# awareness16.net
KiCad netlist of a schematic drawn in EAGLE
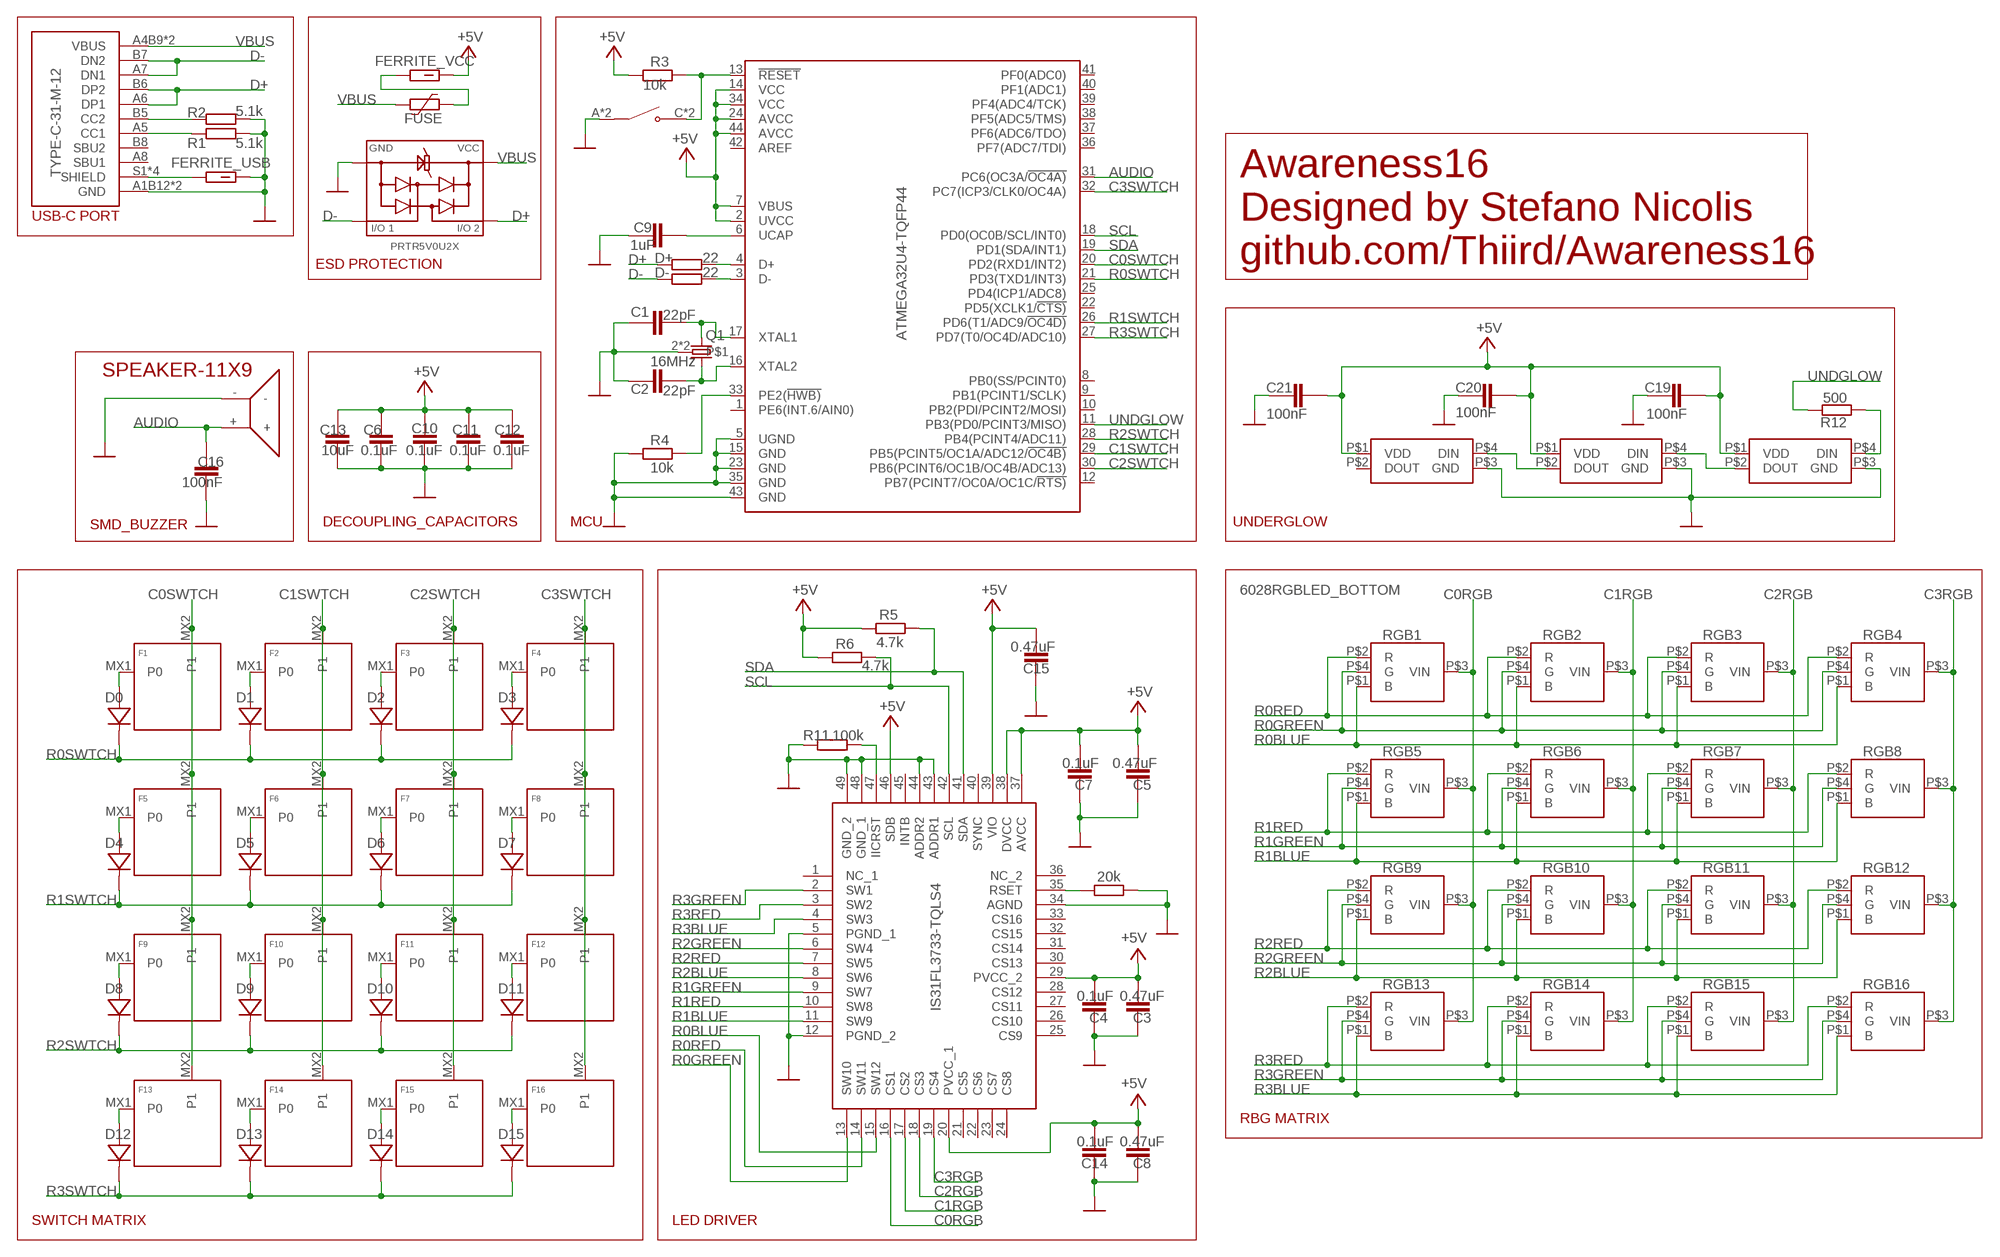
[diagram p0: schematic, sheet 1]

(export (version "E")
  (design (tool "Eeschema 10.0.6"))
  (components
    (comp (ref "C1")
      (value "22pF")
      (footprint "eagle-import:C0603")
      (libsource (lib "eagle-import") (part "CAPACITOR-0603"))
    )
    (comp (ref "C2")
      (value "22pF")
      (footprint "eagle-import:C0603")
      (libsource (lib "eagle-import") (part "CAPACITOR-0603"))
    )
    (comp (ref "C3")
      (value "0.47uF")
      (footprint "eagle-import:C0603")
      (libsource (lib "eagle-import") (part "CAPACITOR-0603"))
    )
    (comp (ref "C4")
      (value "0.1uF")
      (footprint "eagle-import:C0603")
      (libsource (lib "eagle-import") (part "CAPACITOR-0603"))
    )
    (comp (ref "C5")
      (value "0.47uF")
      (footprint "eagle-import:C0603")
      (libsource (lib "eagle-import") (part "CAPACITOR-0603"))
    )
    (comp (ref "C6")
      (value "0.1uF")
      (footprint "eagle-import:C0603")
      (libsource (lib "eagle-import") (part "CAPACITOR-0603"))
    )
    (comp (ref "C7")
      (value "0.1uF")
      (footprint "eagle-import:C0603")
      (libsource (lib "eagle-import") (part "CAPACITOR-0603"))
    )
    (comp (ref "C8")
      (value "0.47uF")
      (footprint "eagle-import:C0603")
      (libsource (lib "eagle-import") (part "CAPACITOR-0603"))
    )
    (comp (ref "C9")
      (value "1uF")
      (footprint "eagle-import:C0603")
      (libsource (lib "eagle-import") (part "CAPACITOR-0603"))
    )
    (comp (ref "C10")
      (value "0.1uF")
      (footprint "eagle-import:C0603")
      (libsource (lib "eagle-import") (part "CAPACITOR-0603"))
    )
    (comp (ref "C11")
      (value "0.1uF")
      (footprint "eagle-import:C0603")
      (libsource (lib "eagle-import") (part "CAPACITOR-0603"))
    )
    (comp (ref "C12")
      (value "0.1uF")
      (footprint "eagle-import:C0603")
      (libsource (lib "eagle-import") (part "CAPACITOR-0603"))
    )
    (comp (ref "C13")
      (value "10uF")
      (footprint "eagle-import:C0603")
      (libsource (lib "eagle-import") (part "CAPACITOR-0603"))
    )
    (comp (ref "C14")
      (value "0.1uF")
      (footprint "eagle-import:C0603")
      (libsource (lib "eagle-import") (part "CAPACITOR-0603"))
    )
    (comp (ref "C15")
      (value "0.47uF")
      (footprint "eagle-import:C0603")
      (libsource (lib "eagle-import") (part "CAPACITOR-0603"))
    )
    (comp (ref "C16")
      (value "100nF")
      (footprint "eagle-import:C0603")
      (libsource (lib "eagle-import") (part "CAPACITOR-0603"))
    )
    (comp (ref "C19")
      (value "100nF")
      (footprint "eagle-import:C0603")
      (libsource (lib "eagle-import") (part "CAPACITOR-0603"))
    )
    (comp (ref "C20")
      (value "100nF")
      (footprint "eagle-import:C0603")
      (libsource (lib "eagle-import") (part "CAPACITOR-0603"))
    )
    (comp (ref "C21")
      (value "100nF")
      (footprint "eagle-import:C0603")
      (libsource (lib "eagle-import") (part "CAPACITOR-0603"))
    )
    (comp (ref "D+")
      (value "22")
      (footprint "eagle-import:R0603")
      (libsource (lib "eagle-import") (part "RESISTOR-0603"))
    )
    (comp (ref "D-")
      (value "22")
      (footprint "eagle-import:R0603")
      (libsource (lib "eagle-import") (part "RESISTOR-0603"))
    )
    (comp (ref "D0")
      (value "DIODE-SOD-123")
      (footprint "eagle-import:SOD-123")
      (libsource (lib "eagle-import") (part "DIODE-SOD-123"))
    )
    (comp (ref "D1")
      (value "DIODE-SOD-123")
      (footprint "eagle-import:SOD-123")
      (libsource (lib "eagle-import") (part "DIODE-SOD-123"))
    )
    (comp (ref "D2")
      (value "DIODE-SOD-123")
      (footprint "eagle-import:SOD-123")
      (libsource (lib "eagle-import") (part "DIODE-SOD-123"))
    )
    (comp (ref "D3")
      (value "DIODE-SOD-123")
      (footprint "eagle-import:SOD-123")
      (libsource (lib "eagle-import") (part "DIODE-SOD-123"))
    )
    (comp (ref "D4")
      (value "DIODE-SOD-123")
      (footprint "eagle-import:SOD-123")
      (libsource (lib "eagle-import") (part "DIODE-SOD-123"))
    )
    (comp (ref "D5")
      (value "DIODE-SOD-123")
      (footprint "eagle-import:SOD-123")
      (libsource (lib "eagle-import") (part "DIODE-SOD-123"))
    )
    (comp (ref "D6")
      (value "DIODE-SOD-123")
      (footprint "eagle-import:SOD-123")
      (libsource (lib "eagle-import") (part "DIODE-SOD-123"))
    )
    (comp (ref "D7")
      (value "DIODE-SOD-123")
      (footprint "eagle-import:SOD-123")
      (libsource (lib "eagle-import") (part "DIODE-SOD-123"))
    )
    (comp (ref "D8")
      (value "DIODE-SOD-123")
      (footprint "eagle-import:SOD-123")
      (libsource (lib "eagle-import") (part "DIODE-SOD-123"))
    )
    (comp (ref "D9")
      (value "DIODE-SOD-123")
      (footprint "eagle-import:SOD-123")
      (libsource (lib "eagle-import") (part "DIODE-SOD-123"))
    )
    (comp (ref "D10")
      (value "DIODE-SOD-123")
      (footprint "eagle-import:SOD-123")
      (libsource (lib "eagle-import") (part "DIODE-SOD-123"))
    )
    (comp (ref "D11")
      (value "DIODE-SOD-123")
      (footprint "eagle-import:SOD-123")
      (libsource (lib "eagle-import") (part "DIODE-SOD-123"))
    )
    (comp (ref "D12")
      (value "DIODE-SOD-123")
      (footprint "eagle-import:SOD-123")
      (libsource (lib "eagle-import") (part "DIODE-SOD-123"))
    )
    (comp (ref "D13")
      (value "DIODE-SOD-123")
      (footprint "eagle-import:SOD-123")
      (libsource (lib "eagle-import") (part "DIODE-SOD-123"))
    )
    (comp (ref "D14")
      (value "DIODE-SOD-123")
      (footprint "eagle-import:SOD-123")
      (libsource (lib "eagle-import") (part "DIODE-SOD-123"))
    )
    (comp (ref "D15")
      (value "DIODE-SOD-123")
      (footprint "eagle-import:SOD-123")
      (libsource (lib "eagle-import") (part "DIODE-SOD-123"))
    )
    (comp (ref "DRIVER")
      (value "IS31FL3733-TQLS4")
      (footprint "eagle-import:QFP50P900X900X120-49N")
      (fields (field (name "MOUSER_PART_NUMBER") "870-IS31FL3733-TQLS4"))
      (libsource (lib "eagle-import") (part "IS31FL3733-TQLS4"))
    )
    (comp (ref "F1")
      (value "KEYSWITCH-PLAIN-MX-1U")
      (footprint "eagle-import:MX-1U")
      (libsource (lib "eagle-import") (part "KEYSWITCH-PLAIN-MX-1U"))
    )
    (comp (ref "F2")
      (value "KEYSWITCH-PLAIN-MX-1U")
      (footprint "eagle-import:MX-1U")
      (libsource (lib "eagle-import") (part "KEYSWITCH-PLAIN-MX-1U"))
    )
    (comp (ref "F3")
      (value "KEYSWITCH-PLAIN-MX-1U")
      (footprint "eagle-import:MX-1U")
      (libsource (lib "eagle-import") (part "KEYSWITCH-PLAIN-MX-1U"))
    )
    (comp (ref "F4")
      (value "KEYSWITCH-PLAIN-MX-1U")
      (footprint "eagle-import:MX-1U")
      (libsource (lib "eagle-import") (part "KEYSWITCH-PLAIN-MX-1U"))
    )
    (comp (ref "F5")
      (value "KEYSWITCH-PLAIN-MX-1U")
      (footprint "eagle-import:MX-1U")
      (libsource (lib "eagle-import") (part "KEYSWITCH-PLAIN-MX-1U"))
    )
    (comp (ref "F6")
      (value "KEYSWITCH-PLAIN-MX-1U")
      (footprint "eagle-import:MX-1U")
      (libsource (lib "eagle-import") (part "KEYSWITCH-PLAIN-MX-1U"))
    )
    (comp (ref "F7")
      (value "KEYSWITCH-PLAIN-MX-1U")
      (footprint "eagle-import:MX-1U")
      (libsource (lib "eagle-import") (part "KEYSWITCH-PLAIN-MX-1U"))
    )
    (comp (ref "F8")
      (value "KEYSWITCH-PLAIN-MX-1U")
      (footprint "eagle-import:MX-1U")
      (libsource (lib "eagle-import") (part "KEYSWITCH-PLAIN-MX-1U"))
    )
    (comp (ref "F9")
      (value "KEYSWITCH-PLAIN-MX-1U")
      (footprint "eagle-import:MX-1U")
      (libsource (lib "eagle-import") (part "KEYSWITCH-PLAIN-MX-1U"))
    )
    (comp (ref "F10")
      (value "KEYSWITCH-PLAIN-MX-1U")
      (footprint "eagle-import:MX-1U")
      (libsource (lib "eagle-import") (part "KEYSWITCH-PLAIN-MX-1U"))
    )
    (comp (ref "F11")
      (value "KEYSWITCH-PLAIN-MX-1U")
      (footprint "eagle-import:MX-1U")
      (libsource (lib "eagle-import") (part "KEYSWITCH-PLAIN-MX-1U"))
    )
    (comp (ref "F12")
      (value "KEYSWITCH-PLAIN-MX-1U")
      (footprint "eagle-import:MX-1U")
      (libsource (lib "eagle-import") (part "KEYSWITCH-PLAIN-MX-1U"))
    )
    (comp (ref "F13")
      (value "KEYSWITCH-PLAIN-MX-1U")
      (footprint "eagle-import:MX-1U")
      (libsource (lib "eagle-import") (part "KEYSWITCH-PLAIN-MX-1U"))
    )
    (comp (ref "F14")
      (value "KEYSWITCH-PLAIN-MX-1U")
      (footprint "eagle-import:MX-1U")
      (libsource (lib "eagle-import") (part "KEYSWITCH-PLAIN-MX-1U"))
    )
    (comp (ref "F15")
      (value "KEYSWITCH-PLAIN-MX-1U")
      (footprint "eagle-import:MX-1U")
      (libsource (lib "eagle-import") (part "KEYSWITCH-PLAIN-MX-1U"))
    )
    (comp (ref "F16")
      (value "KEYSWITCH-PLAIN-MX-1U")
      (footprint "eagle-import:MX-1U")
      (libsource (lib "eagle-import") (part "KEYSWITCH-PLAIN-MX-1U"))
    )
    (comp (ref "FERRITE_USB")
      (value "FERRITE_BEAD")
      (footprint "eagle-import:BEADC1608X95N")
      (libsource (lib "eagle-import") (part "FBCHIP-0603(1608-METRIC)"))
    )
    (comp (ref "FERRITE_VCC")
      (value "FERRITE_BEAD")
      (footprint "eagle-import:BEADC1608X95N")
      (libsource (lib "eagle-import") (part "FBCHIP-0603(1608-METRIC)"))
    )
    (comp (ref "FUSE")
      (value "0603L050")
      (footprint "eagle-import:0603L")
      (fields (field (name "MF") "Littelfuse"))
      (libsource (lib "eagle-import") (part "?0603L050"))
    )
    (comp (ref "J1")
      (value "TYPE-C-31-M-12")
      (footprint "eagle-import:HRO_TYPE-C-31-M-12")
      (fields (field (name "MF") "HRO Electronics Co., Ltd."))
      (libsource (lib "eagle-import") (part "TYPE-C-31-M-12"))
    )
    (comp (ref "MCU")
      (value "ATMEGA32U4-TQFP44")
      (footprint "eagle-import:TQFP44-0.8-9.6X9.6MM")
      (fields (field (name "MPN") "ATMEGA32U4"))
      (libsource (lib "eagle-import") (part "MCU-ATMEGA32U4-AU(TQFP44)"))
    )
    (comp (ref "Q1")
      (value "16MHz")
      (footprint "eagle-import:2.0X1.6_KX-5")
      (libsource (lib "eagle-import") (part "KX-5"))
    )
    (comp (ref "R1")
      (value "5.1k")
      (footprint "eagle-import:R0603")
      (libsource (lib "eagle-import") (part "RESISTOR-0603"))
    )
    (comp (ref "R2")
      (value "5.1k")
      (footprint "eagle-import:R0603")
      (libsource (lib "eagle-import") (part "RESISTOR-0603"))
    )
    (comp (ref "R3")
      (value "10k")
      (footprint "eagle-import:R0603")
      (libsource (lib "eagle-import") (part "RESISTOR-0603"))
    )
    (comp (ref "R4")
      (value "10k")
      (footprint "eagle-import:R0603")
      (libsource (lib "eagle-import") (part "RESISTOR-0603"))
    )
    (comp (ref "R5")
      (value "4.7k")
      (footprint "eagle-import:R0603")
      (libsource (lib "eagle-import") (part "RESISTOR-0603"))
    )
    (comp (ref "R6")
      (value "4.7k")
      (footprint "eagle-import:R0603")
      (libsource (lib "eagle-import") (part "RESISTOR-0603"))
    )
    (comp (ref "R11")
      (value "100k")
      (footprint "eagle-import:R0603")
      (libsource (lib "eagle-import") (part "RESISTOR-0603"))
    )
    (comp (ref "R12")
      (value "500")
      (footprint "eagle-import:R0603")
      (libsource (lib "eagle-import") (part "RESISTOR-0603"))
    )
    (comp (ref "RESET")
      (value "20k")
      (footprint "eagle-import:R0603")
      (libsource (lib "eagle-import") (part "RESISTOR-0603"))
    )
    (comp (ref "RGB1")
      (value "6028RGBLED_BOTTOM")
      (footprint "eagle-import:6028RGBLED_BOTTOM")
      (libsource (lib "eagle-import") (part "6028RGBLED_BOTTOM"))
    )
    (comp (ref "RGB2")
      (value "6028RGBLED_BOTTOM")
      (footprint "eagle-import:6028RGBLED_BOTTOM")
      (libsource (lib "eagle-import") (part "6028RGBLED_BOTTOM"))
    )
    (comp (ref "RGB3")
      (value "6028RGBLED_BOTTOM")
      (footprint "eagle-import:6028RGBLED_BOTTOM")
      (libsource (lib "eagle-import") (part "6028RGBLED_BOTTOM"))
    )
    (comp (ref "RGB4")
      (value "6028RGBLED_BOTTOM")
      (footprint "eagle-import:6028RGBLED_BOTTOM")
      (libsource (lib "eagle-import") (part "6028RGBLED_BOTTOM"))
    )
    (comp (ref "RGB5")
      (value "6028RGBLED_BOTTOM")
      (footprint "eagle-import:6028RGBLED_BOTTOM")
      (libsource (lib "eagle-import") (part "6028RGBLED_BOTTOM"))
    )
    (comp (ref "RGB6")
      (value "6028RGBLED_BOTTOM")
      (footprint "eagle-import:6028RGBLED_BOTTOM")
      (libsource (lib "eagle-import") (part "6028RGBLED_BOTTOM"))
    )
    (comp (ref "RGB7")
      (value "6028RGBLED_BOTTOM")
      (footprint "eagle-import:6028RGBLED_BOTTOM")
      (libsource (lib "eagle-import") (part "6028RGBLED_BOTTOM"))
    )
    (comp (ref "RGB8")
      (value "6028RGBLED_BOTTOM")
      (footprint "eagle-import:6028RGBLED_BOTTOM")
      (libsource (lib "eagle-import") (part "6028RGBLED_BOTTOM"))
    )
    (comp (ref "RGB9")
      (value "6028RGBLED_BOTTOM")
      (footprint "eagle-import:6028RGBLED_BOTTOM")
      (libsource (lib "eagle-import") (part "6028RGBLED_BOTTOM"))
    )
    (comp (ref "RGB10")
      (value "6028RGBLED_BOTTOM")
      (footprint "eagle-import:6028RGBLED_BOTTOM")
      (libsource (lib "eagle-import") (part "6028RGBLED_BOTTOM"))
    )
    (comp (ref "RGB11")
      (value "6028RGBLED_BOTTOM")
      (footprint "eagle-import:6028RGBLED_BOTTOM")
      (libsource (lib "eagle-import") (part "6028RGBLED_BOTTOM"))
    )
    (comp (ref "RGB12")
      (value "6028RGBLED_BOTTOM")
      (footprint "eagle-import:6028RGBLED_BOTTOM")
      (libsource (lib "eagle-import") (part "6028RGBLED_BOTTOM"))
    )
    (comp (ref "RGB13")
      (value "6028RGBLED_BOTTOM")
      (footprint "eagle-import:6028RGBLED_BOTTOM")
      (libsource (lib "eagle-import") (part "6028RGBLED_BOTTOM"))
    )
    (comp (ref "RGB14")
      (value "6028RGBLED_BOTTOM")
      (footprint "eagle-import:6028RGBLED_BOTTOM")
      (libsource (lib "eagle-import") (part "6028RGBLED_BOTTOM"))
    )
    (comp (ref "RGB15")
      (value "6028RGBLED_BOTTOM")
      (footprint "eagle-import:6028RGBLED_BOTTOM")
      (libsource (lib "eagle-import") (part "6028RGBLED_BOTTOM"))
    )
    (comp (ref "RGB16")
      (value "6028RGBLED_BOTTOM")
      (footprint "eagle-import:6028RGBLED_BOTTOM")
      (libsource (lib "eagle-import") (part "6028RGBLED_BOTTOM"))
    )
    (comp (ref "S1")
      (value "TS-1187A-B-A-B")
      (footprint "eagle-import:SW_TS-1187A-B-A-B")
      (fields (field (name "MF") "XKB Industrial Precision"))
      (libsource (lib "eagle-import") (part "TS-1187A-B-A-B"))
    )
    (comp (ref "SP1")
      (value "SPEAKER-11X9")
      (footprint "eagle-import:AST1109MLTRQ")
      (libsource (lib "eagle-import") (part "SPEAKER-SMD-11X9"))
    )
    (comp (ref "U$1")
      (value "PRTR5V0U2X")
      (footprint "eagle-import:PRTR5V0U2X")
      (libsource (lib "eagle-import") (part "PRTR5V0U2X"))
    )
    (comp (ref "UGLOW1")
      (value "SK6812MINI-E")
      (footprint "eagle-import:SK6812MINI-E")
      (libsource (lib "eagle-import") (part "SK6812MINI-E"))
    )
    (comp (ref "UGLOW2")
      (value "SK6812MINI-E")
      (footprint "eagle-import:SK6812MINI-E")
      (libsource (lib "eagle-import") (part "SK6812MINI-E"))
    )
    (comp (ref "UGLOW3")
      (value "SK6812MINI-E")
      (footprint "eagle-import:SK6812MINI-E")
      (libsource (lib "eagle-import") (part "SK6812MINI-E"))
    )
  )
  (nets
    (net (code "1") (name "+5V") (class "Default")
      (node (ref "C10") (pin "1") (pinfunction "1_1") (pintype "passive"))
      (node (ref "C11") (pin "1") (pinfunction "1_1") (pintype "passive"))
      (node (ref "C12") (pin "1") (pinfunction "1_1") (pintype "passive"))
      (node (ref "C13") (pin "1") (pinfunction "1_1") (pintype "passive"))
      (node (ref "C14") (pin "2") (pinfunction "2_2") (pintype "passive"))
      (node (ref "C15") (pin "2") (pinfunction "2_2") (pintype "passive"))
      (node (ref "C19") (pin "2") (pinfunction "2_2") (pintype "passive"))
      (node (ref "C20") (pin "2") (pinfunction "2_2") (pintype "passive"))
      (node (ref "C21") (pin "2") (pinfunction "2_2") (pintype "passive"))
      (node (ref "C3") (pin "2") (pinfunction "2_2") (pintype "passive"))
      (node (ref "C4") (pin "2") (pinfunction "2_2") (pintype "passive"))
      (node (ref "C5") (pin "2") (pinfunction "2_2") (pintype "passive"))
      (node (ref "C6") (pin "1") (pinfunction "1_1") (pintype "passive"))
      (node (ref "C7") (pin "2") (pinfunction "2_2") (pintype "passive"))
      (node (ref "C8") (pin "2") (pinfunction "2_2") (pintype "passive"))
      (node (ref "DRIVER") (pin "20") (pinfunction "PVCC_1_20") (pintype "bidirectional"))
      (node (ref "DRIVER") (pin "29") (pinfunction "PVCC_2_29") (pintype "bidirectional"))
      (node (ref "DRIVER") (pin "37") (pinfunction "AVCC_37") (pintype "bidirectional"))
      (node (ref "DRIVER") (pin "38") (pinfunction "DVCC_38") (pintype "bidirectional"))
      (node (ref "DRIVER") (pin "39") (pinfunction "VIO_39") (pintype "bidirectional"))
      (node (ref "DRIVER") (pin "46") (pinfunction "SDB_46") (pintype "bidirectional"))
      (node (ref "FERRITE_VCC") (pin "2") (pinfunction "2_2") (pintype "passive"))
      (node (ref "MCU") (pin "14") (pinfunction "VCC_14") (pintype "bidirectional"))
      (node (ref "MCU") (pin "2") (pinfunction "UVCC_2") (pintype "bidirectional"))
      (node (ref "MCU") (pin "24") (pinfunction "AVCC_24") (pintype "bidirectional"))
      (node (ref "MCU") (pin "34") (pinfunction "VCC_34") (pintype "bidirectional"))
      (node (ref "MCU") (pin "44") (pinfunction "AVCC_44") (pintype "bidirectional"))
      (node (ref "MCU") (pin "7") (pinfunction "VBUS_7") (pintype "bidirectional"))
      (node (ref "R3") (pin "1") (pinfunction "1_1") (pintype "passive"))
      (node (ref "R5") (pin "2") (pinfunction "2_2") (pintype "passive"))
      (node (ref "R6") (pin "2") (pinfunction "2_2") (pintype "passive"))
      (node (ref "UGLOW1") (pin "P$1") (pinfunction "VDD_P$1") (pintype "power_in"))
      (node (ref "UGLOW2") (pin "P$1") (pinfunction "VDD_P$1") (pintype "power_in"))
      (node (ref "UGLOW3") (pin "P$1") (pinfunction "VDD_P$1") (pintype "power_in"))
    )
    (net (code "2") (name "/AUDIO") (class "Default")
      (node (ref "C16") (pin "1") (pinfunction "1_1") (pintype "passive"))
      (node (ref "MCU") (pin "31") (pinfunction "PC6(OC3A/~{OC4A})_31") (pintype "bidirectional"))
      (node (ref "SP1") (pin "+") (pinfunction "+_+") (pintype "bidirectional"))
    )
    (net (code "3") (name "/C0RGB") (class "Default")
      (node (ref "DRIVER") (pin "16") (pinfunction "CS1_16") (pintype "bidirectional"))
      (node (ref "RGB1") (pin "P$3") (pinfunction "VIN_P$3") (pintype "power_in"))
      (node (ref "RGB13") (pin "P$3") (pinfunction "VIN_P$3") (pintype "power_in"))
      (node (ref "RGB5") (pin "P$3") (pinfunction "VIN_P$3") (pintype "power_in"))
      (node (ref "RGB9") (pin "P$3") (pinfunction "VIN_P$3") (pintype "power_in"))
    )
    (net (code "4") (name "/C0SWTCH") (class "Default")
      (node (ref "F1") (pin "MX2") (pinfunction "P1_MX2") (pintype "bidirectional"))
      (node (ref "F13") (pin "MX2") (pinfunction "P1_MX2") (pintype "bidirectional"))
      (node (ref "F5") (pin "MX2") (pinfunction "P1_MX2") (pintype "bidirectional"))
      (node (ref "F9") (pin "MX2") (pinfunction "P1_MX2") (pintype "bidirectional"))
      (node (ref "MCU") (pin "20") (pinfunction "PD2(RXD1/INT2)_20") (pintype "bidirectional"))
    )
    (net (code "5") (name "/C1RGB") (class "Default")
      (node (ref "DRIVER") (pin "17") (pinfunction "CS2_17") (pintype "bidirectional"))
      (node (ref "RGB10") (pin "P$3") (pinfunction "VIN_P$3") (pintype "power_in"))
      (node (ref "RGB14") (pin "P$3") (pinfunction "VIN_P$3") (pintype "power_in"))
      (node (ref "RGB2") (pin "P$3") (pinfunction "VIN_P$3") (pintype "power_in"))
      (node (ref "RGB6") (pin "P$3") (pinfunction "VIN_P$3") (pintype "power_in"))
    )
    (net (code "6") (name "/C1SWTCH") (class "Default")
      (node (ref "F10") (pin "MX2") (pinfunction "P1_MX2") (pintype "bidirectional"))
      (node (ref "F14") (pin "MX2") (pinfunction "P1_MX2") (pintype "bidirectional"))
      (node (ref "F2") (pin "MX2") (pinfunction "P1_MX2") (pintype "bidirectional"))
      (node (ref "F6") (pin "MX2") (pinfunction "P1_MX2") (pintype "bidirectional"))
      (node (ref "MCU") (pin "29") (pinfunction "PB5(PCINT5/OC1A/ADC12/~{OC4B})_29") (pintype "bidirectional"))
    )
    (net (code "7") (name "/C2RGB") (class "Default")
      (node (ref "DRIVER") (pin "18") (pinfunction "CS3_18") (pintype "bidirectional"))
      (node (ref "RGB11") (pin "P$3") (pinfunction "VIN_P$3") (pintype "power_in"))
      (node (ref "RGB15") (pin "P$3") (pinfunction "VIN_P$3") (pintype "power_in"))
      (node (ref "RGB3") (pin "P$3") (pinfunction "VIN_P$3") (pintype "power_in"))
      (node (ref "RGB7") (pin "P$3") (pinfunction "VIN_P$3") (pintype "power_in"))
    )
    (net (code "8") (name "/C2SWTCH") (class "Default")
      (node (ref "F11") (pin "MX2") (pinfunction "P1_MX2") (pintype "bidirectional"))
      (node (ref "F15") (pin "MX2") (pinfunction "P1_MX2") (pintype "bidirectional"))
      (node (ref "F3") (pin "MX2") (pinfunction "P1_MX2") (pintype "bidirectional"))
      (node (ref "F7") (pin "MX2") (pinfunction "P1_MX2") (pintype "bidirectional"))
      (node (ref "MCU") (pin "30") (pinfunction "PB6(PCINT6/OC1B/OC4B/ADC13)_30") (pintype "bidirectional"))
    )
    (net (code "9") (name "/C3RGB") (class "Default")
      (node (ref "DRIVER") (pin "19") (pinfunction "CS4_19") (pintype "bidirectional"))
      (node (ref "RGB12") (pin "P$3") (pinfunction "VIN_P$3") (pintype "power_in"))
      (node (ref "RGB16") (pin "P$3") (pinfunction "VIN_P$3") (pintype "power_in"))
      (node (ref "RGB4") (pin "P$3") (pinfunction "VIN_P$3") (pintype "power_in"))
      (node (ref "RGB8") (pin "P$3") (pinfunction "VIN_P$3") (pintype "power_in"))
    )
    (net (code "10") (name "/C3SWTCH") (class "Default")
      (node (ref "F12") (pin "MX2") (pinfunction "P1_MX2") (pintype "bidirectional"))
      (node (ref "F16") (pin "MX2") (pinfunction "P1_MX2") (pintype "bidirectional"))
      (node (ref "F4") (pin "MX2") (pinfunction "P1_MX2") (pintype "bidirectional"))
      (node (ref "F8") (pin "MX2") (pinfunction "P1_MX2") (pintype "bidirectional"))
      (node (ref "MCU") (pin "32") (pinfunction "PC7(ICP3/CLK0/OC4A)_32") (pintype "bidirectional"))
    )
    (net (code "11") (name "/D+") (class "Default")
      (node (ref "D+") (pin "1") (pinfunction "1_1") (pintype "passive"))
      (node (ref "J1") (pin "A6") (pinfunction "DP1_A6") (pintype "bidirectional"))
      (node (ref "J1") (pin "B6") (pinfunction "DP2_B6") (pintype "bidirectional"))
      (node (ref "U$1") (pin "3") (pinfunction "3_3") (pintype "bidirectional"))
    )
    (net (code "12") (name "/D-") (class "Default")
      (node (ref "D-") (pin "1") (pinfunction "1_1") (pintype "passive"))
      (node (ref "J1") (pin "A7") (pinfunction "DN1_A7") (pintype "bidirectional"))
      (node (ref "J1") (pin "B7") (pinfunction "DN2_B7") (pintype "bidirectional"))
      (node (ref "U$1") (pin "2") (pinfunction "2_2") (pintype "bidirectional"))
    )
    (net (code "13") (name "/N$24") (class "Default")
      (node (ref "FERRITE_USB") (pin "1") (pinfunction "1_1") (pintype "passive"))
      (node (ref "J1") (pin "A5") (pinfunction "CC1_A5") (pintype "bidirectional"))
      (node (ref "J1") (pin "B5") (pinfunction "CC2_B5") (pintype "bidirectional"))
      (node (ref "J1") (pin "S1") (pinfunction "SHIELD_S1") (pintype "passive"))
      (node (ref "J1") (pin "S2") (pinfunction "SHIELD_S2") (pintype "passive"))
      (node (ref "J1") (pin "S3") (pinfunction "SHIELD_S3") (pintype "passive"))
      (node (ref "J1") (pin "S4") (pinfunction "SHIELD_S4") (pintype "passive"))
      (node (ref "R1") (pin "2") (pinfunction "2_2") (pintype "passive"))
      (node (ref "R2") (pin "2") (pinfunction "2_2") (pintype "passive"))
    )
    (net (code "14") (name "/R0BLUE") (class "Default")
      (node (ref "DRIVER") (pin "15") (pinfunction "SW12_15") (pintype "bidirectional"))
      (node (ref "RGB1") (pin "P$1") (pinfunction "B_P$1") (pintype "bidirectional"))
      (node (ref "RGB2") (pin "P$1") (pinfunction "B_P$1") (pintype "bidirectional"))
      (node (ref "RGB3") (pin "P$1") (pinfunction "B_P$1") (pintype "bidirectional"))
      (node (ref "RGB4") (pin "P$1") (pinfunction "B_P$1") (pintype "bidirectional"))
    )
    (net (code "15") (name "/R0GREEN") (class "Default")
      (node (ref "DRIVER") (pin "13") (pinfunction "SW10_13") (pintype "bidirectional"))
      (node (ref "RGB1") (pin "P$4") (pinfunction "G_P$4") (pintype "output"))
      (node (ref "RGB2") (pin "P$4") (pinfunction "G_P$4") (pintype "output"))
      (node (ref "RGB3") (pin "P$4") (pinfunction "G_P$4") (pintype "output"))
      (node (ref "RGB4") (pin "P$4") (pinfunction "G_P$4") (pintype "output"))
    )
    (net (code "16") (name "/R0RED") (class "Default")
      (node (ref "DRIVER") (pin "14") (pinfunction "SW11_14") (pintype "bidirectional"))
      (node (ref "RGB1") (pin "P$2") (pinfunction "R_P$2") (pintype "power_in"))
      (node (ref "RGB2") (pin "P$2") (pinfunction "R_P$2") (pintype "power_in"))
      (node (ref "RGB3") (pin "P$2") (pinfunction "R_P$2") (pintype "power_in"))
      (node (ref "RGB4") (pin "P$2") (pinfunction "R_P$2") (pintype "power_in"))
    )
    (net (code "17") (name "/R0SWTCH") (class "Default")
      (node (ref "D0") (pin "C") (pinfunction "C_C") (pintype "passive"))
      (node (ref "D1") (pin "C") (pinfunction "C_C") (pintype "passive"))
      (node (ref "D2") (pin "C") (pinfunction "C_C") (pintype "passive"))
      (node (ref "D3") (pin "C") (pinfunction "C_C") (pintype "passive"))
      (node (ref "MCU") (pin "21") (pinfunction "PD3(TXD1/INT3)_21") (pintype "bidirectional"))
    )
    (net (code "18") (name "/R1BLUE") (class "Default")
      (node (ref "DRIVER") (pin "11") (pinfunction "SW9_11") (pintype "bidirectional"))
      (node (ref "RGB5") (pin "P$1") (pinfunction "B_P$1") (pintype "bidirectional"))
      (node (ref "RGB6") (pin "P$1") (pinfunction "B_P$1") (pintype "bidirectional"))
      (node (ref "RGB7") (pin "P$1") (pinfunction "B_P$1") (pintype "bidirectional"))
      (node (ref "RGB8") (pin "P$1") (pinfunction "B_P$1") (pintype "bidirectional"))
    )
    (net (code "19") (name "/R1GREEN") (class "Default")
      (node (ref "DRIVER") (pin "9") (pinfunction "SW7_9") (pintype "bidirectional"))
      (node (ref "RGB5") (pin "P$4") (pinfunction "G_P$4") (pintype "output"))
      (node (ref "RGB6") (pin "P$4") (pinfunction "G_P$4") (pintype "output"))
      (node (ref "RGB7") (pin "P$4") (pinfunction "G_P$4") (pintype "output"))
      (node (ref "RGB8") (pin "P$4") (pinfunction "G_P$4") (pintype "output"))
    )
    (net (code "20") (name "/R1RED") (class "Default")
      (node (ref "DRIVER") (pin "10") (pinfunction "SW8_10") (pintype "bidirectional"))
      (node (ref "RGB5") (pin "P$2") (pinfunction "R_P$2") (pintype "power_in"))
      (node (ref "RGB6") (pin "P$2") (pinfunction "R_P$2") (pintype "power_in"))
      (node (ref "RGB7") (pin "P$2") (pinfunction "R_P$2") (pintype "power_in"))
      (node (ref "RGB8") (pin "P$2") (pinfunction "R_P$2") (pintype "power_in"))
    )
    (net (code "21") (name "/R1SWTCH") (class "Default")
      (node (ref "D4") (pin "C") (pinfunction "C_C") (pintype "passive"))
      (node (ref "D5") (pin "C") (pinfunction "C_C") (pintype "passive"))
      (node (ref "D6") (pin "C") (pinfunction "C_C") (pintype "passive"))
      (node (ref "D7") (pin "C") (pinfunction "C_C") (pintype "passive"))
      (node (ref "MCU") (pin "26") (pinfunction "PD6(T1/ADC9/~{OC4D})_26") (pintype "bidirectional"))
    )
    (net (code "22") (name "/R2BLUE") (class "Default")
      (node (ref "DRIVER") (pin "8") (pinfunction "SW6_8") (pintype "bidirectional"))
      (node (ref "RGB10") (pin "P$1") (pinfunction "B_P$1") (pintype "bidirectional"))
      (node (ref "RGB11") (pin "P$1") (pinfunction "B_P$1") (pintype "bidirectional"))
      (node (ref "RGB12") (pin "P$1") (pinfunction "B_P$1") (pintype "bidirectional"))
      (node (ref "RGB9") (pin "P$1") (pinfunction "B_P$1") (pintype "bidirectional"))
    )
    (net (code "23") (name "/R2GREEN") (class "Default")
      (node (ref "DRIVER") (pin "6") (pinfunction "SW4_6") (pintype "bidirectional"))
      (node (ref "RGB10") (pin "P$4") (pinfunction "G_P$4") (pintype "output"))
      (node (ref "RGB11") (pin "P$4") (pinfunction "G_P$4") (pintype "output"))
      (node (ref "RGB12") (pin "P$4") (pinfunction "G_P$4") (pintype "output"))
      (node (ref "RGB9") (pin "P$4") (pinfunction "G_P$4") (pintype "output"))
    )
    (net (code "24") (name "/R2RED") (class "Default")
      (node (ref "DRIVER") (pin "7") (pinfunction "SW5_7") (pintype "bidirectional"))
      (node (ref "RGB10") (pin "P$2") (pinfunction "R_P$2") (pintype "power_in"))
      (node (ref "RGB11") (pin "P$2") (pinfunction "R_P$2") (pintype "power_in"))
      (node (ref "RGB12") (pin "P$2") (pinfunction "R_P$2") (pintype "power_in"))
      (node (ref "RGB9") (pin "P$2") (pinfunction "R_P$2") (pintype "power_in"))
    )
    (net (code "25") (name "/R2SWTCH") (class "Default")
      (node (ref "D10") (pin "C") (pinfunction "C_C") (pintype "passive"))
      (node (ref "D11") (pin "C") (pinfunction "C_C") (pintype "passive"))
      (node (ref "D8") (pin "C") (pinfunction "C_C") (pintype "passive"))
      (node (ref "D9") (pin "C") (pinfunction "C_C") (pintype "passive"))
      (node (ref "MCU") (pin "28") (pinfunction "PB4(PCINT4/ADC11)_28") (pintype "bidirectional"))
    )
    (net (code "26") (name "/R3BLUE") (class "Default")
      (node (ref "DRIVER") (pin "4") (pinfunction "SW3_4") (pintype "bidirectional"))
      (node (ref "RGB13") (pin "P$1") (pinfunction "B_P$1") (pintype "bidirectional"))
      (node (ref "RGB14") (pin "P$1") (pinfunction "B_P$1") (pintype "bidirectional"))
      (node (ref "RGB15") (pin "P$1") (pinfunction "B_P$1") (pintype "bidirectional"))
      (node (ref "RGB16") (pin "P$1") (pinfunction "B_P$1") (pintype "bidirectional"))
    )
    (net (code "27") (name "/R3GREEN") (class "Default")
      (node (ref "DRIVER") (pin "2") (pinfunction "SW1_2") (pintype "bidirectional"))
      (node (ref "RGB13") (pin "P$4") (pinfunction "G_P$4") (pintype "output"))
      (node (ref "RGB14") (pin "P$4") (pinfunction "G_P$4") (pintype "output"))
      (node (ref "RGB15") (pin "P$4") (pinfunction "G_P$4") (pintype "output"))
      (node (ref "RGB16") (pin "P$4") (pinfunction "G_P$4") (pintype "output"))
    )
    (net (code "28") (name "/R3RED") (class "Default")
      (node (ref "DRIVER") (pin "3") (pinfunction "SW2_3") (pintype "bidirectional"))
      (node (ref "RGB13") (pin "P$2") (pinfunction "R_P$2") (pintype "power_in"))
      (node (ref "RGB14") (pin "P$2") (pinfunction "R_P$2") (pintype "power_in"))
      (node (ref "RGB15") (pin "P$2") (pinfunction "R_P$2") (pintype "power_in"))
      (node (ref "RGB16") (pin "P$2") (pinfunction "R_P$2") (pintype "power_in"))
    )
    (net (code "29") (name "/R3SWTCH") (class "Default")
      (node (ref "D12") (pin "C") (pinfunction "C_C") (pintype "passive"))
      (node (ref "D13") (pin "C") (pinfunction "C_C") (pintype "passive"))
      (node (ref "D14") (pin "C") (pinfunction "C_C") (pintype "passive"))
      (node (ref "D15") (pin "C") (pinfunction "C_C") (pintype "passive"))
      (node (ref "MCU") (pin "27") (pinfunction "PD7(T0/OC4D/ADC10)_27") (pintype "bidirectional"))
    )
    (net (code "30") (name "/SCL") (class "Default")
      (node (ref "DRIVER") (pin "42") (pinfunction "SCL_42") (pintype "bidirectional"))
      (node (ref "MCU") (pin "18") (pinfunction "PD0(OC0B/SCL/INT0)_18") (pintype "bidirectional"))
      (node (ref "R6") (pin "1") (pinfunction "1_1") (pintype "passive"))
    )
    (net (code "31") (name "/SDA") (class "Default")
      (node (ref "DRIVER") (pin "41") (pinfunction "SDA_41") (pintype "bidirectional"))
      (node (ref "MCU") (pin "19") (pinfunction "PD1(SDA/INT1)_19") (pintype "bidirectional"))
      (node (ref "R5") (pin "1") (pinfunction "1_1") (pintype "passive"))
    )
    (net (code "32") (name "/UNDGLOW") (class "Default")
      (node (ref "MCU") (pin "11") (pinfunction "PB3(PD0/PCINT3/MISO)_11") (pintype "bidirectional"))
      (node (ref "R12") (pin "2") (pinfunction "2_2") (pintype "passive"))
    )
    (net (code "33") (name "/VBUS") (class "Default")
      (node (ref "FUSE") (pin "2") (pinfunction "2_2") (pintype "passive"))
      (node (ref "J1") (pin "A4B9") (pinfunction "VBUS_A4B9") (pintype "power_in"))
      (node (ref "J1") (pin "B4A9") (pinfunction "VBUS_B4A9") (pintype "power_in"))
      (node (ref "U$1") (pin "4") (pinfunction "4_4") (pintype "bidirectional"))
    )
    (net (code "34") (name "GND") (class "Default")
      (node (ref "C1") (pin "1") (pinfunction "1_1") (pintype "passive"))
      (node (ref "C10") (pin "2") (pinfunction "2_2") (pintype "passive"))
      (node (ref "C11") (pin "2") (pinfunction "2_2") (pintype "passive"))
      (node (ref "C12") (pin "2") (pinfunction "2_2") (pintype "passive"))
      (node (ref "C13") (pin "2") (pinfunction "2_2") (pintype "passive"))
      (node (ref "C14") (pin "1") (pinfunction "1_1") (pintype "passive"))
      (node (ref "C15") (pin "1") (pinfunction "1_1") (pintype "passive"))
      (node (ref "C16") (pin "2") (pinfunction "2_2") (pintype "passive"))
      (node (ref "C19") (pin "1") (pinfunction "1_1") (pintype "passive"))
      (node (ref "C2") (pin "1") (pinfunction "1_1") (pintype "passive"))
      (node (ref "C20") (pin "1") (pinfunction "1_1") (pintype "passive"))
      (node (ref "C21") (pin "1") (pinfunction "1_1") (pintype "passive"))
      (node (ref "C3") (pin "1") (pinfunction "1_1") (pintype "passive"))
      (node (ref "C4") (pin "1") (pinfunction "1_1") (pintype "passive"))
      (node (ref "C5") (pin "1") (pinfunction "1_1") (pintype "passive"))
      (node (ref "C6") (pin "2") (pinfunction "2_2") (pintype "passive"))
      (node (ref "C7") (pin "1") (pinfunction "1_1") (pintype "passive"))
      (node (ref "C8") (pin "1") (pinfunction "1_1") (pintype "passive"))
      (node (ref "C9") (pin "1") (pinfunction "1_1") (pintype "passive"))
      (node (ref "DRIVER") (pin "12") (pinfunction "PGND_2_12") (pintype "bidirectional"))
      (node (ref "DRIVER") (pin "34") (pinfunction "AGND_34") (pintype "bidirectional"))
      (node (ref "DRIVER") (pin "43") (pinfunction "ADDR1_43") (pintype "bidirectional"))
      (node (ref "DRIVER") (pin "44") (pinfunction "ADDR2_44") (pintype "bidirectional"))
      (node (ref "DRIVER") (pin "48") (pinfunction "GND_1_48") (pintype "bidirectional"))
      (node (ref "DRIVER") (pin "49") (pinfunction "GND_2_49") (pintype "bidirectional"))
      (node (ref "DRIVER") (pin "5") (pinfunction "PGND_1_5") (pintype "bidirectional"))
      (node (ref "FERRITE_USB") (pin "2") (pinfunction "2_2") (pintype "passive"))
      (node (ref "J1") (pin "A1B12") (pinfunction "GND_A1B12") (pintype "power_in"))
      (node (ref "J1") (pin "B1A12") (pinfunction "GND_B1A12") (pintype "power_in"))
      (node (ref "MCU") (pin "15") (pinfunction "GND_15") (pintype "bidirectional"))
      (node (ref "MCU") (pin "23") (pinfunction "GND_23") (pintype "bidirectional"))
      (node (ref "MCU") (pin "35") (pinfunction "GND_35") (pintype "bidirectional"))
      (node (ref "MCU") (pin "43") (pinfunction "GND_43") (pintype "bidirectional"))
      (node (ref "MCU") (pin "5") (pinfunction "UGND_5") (pintype "bidirectional"))
      (node (ref "Q1") (pin "2") (pinfunction "P$1_2") (pintype "power_in"))
      (node (ref "Q1") (pin "4") (pinfunction "P$1_4") (pintype "power_in"))
      (node (ref "R1") (pin "1") (pinfunction "1_1") (pintype "passive"))
      (node (ref "R11") (pin "1") (pinfunction "1_1") (pintype "passive"))
      (node (ref "R2") (pin "1") (pinfunction "1_1") (pintype "passive"))
      (node (ref "R4") (pin "1") (pinfunction "1_1") (pintype "passive"))
      (node (ref "RESET") (pin "2") (pinfunction "2_2") (pintype "passive"))
      (node (ref "S1") (pin "A") (pinfunction "COM_A") (pintype "passive"))
      (node (ref "S1") (pin "B") (pinfunction "COM_B") (pintype "passive"))
      (node (ref "SP1") (pin "-") (pinfunction "-_-") (pintype "bidirectional"))
      (node (ref "U$1") (pin "1") (pinfunction "1_1") (pintype "bidirectional"))
      (node (ref "UGLOW1") (pin "P$3") (pinfunction "GND_P$3") (pintype "bidirectional"))
      (node (ref "UGLOW2") (pin "P$3") (pinfunction "GND_P$3") (pintype "bidirectional"))
      (node (ref "UGLOW3") (pin "P$3") (pinfunction "GND_P$3") (pintype "bidirectional"))
    )
    (net (code "35") (name "Net-(DRIVER-IICRST)") (class "Default")
      (node (ref "DRIVER") (pin "47") (pinfunction "IICRST_47") (pintype "bidirectional"))
      (node (ref "R11") (pin "2") (pinfunction "2_2") (pintype "passive"))
    )
    (net (code "36") (name "Net-(DRIVER-RSET)") (class "Default")
      (node (ref "DRIVER") (pin "35") (pinfunction "RSET_35") (pintype "bidirectional"))
      (node (ref "RESET") (pin "1") (pinfunction "1_1") (pintype "passive"))
    )
    (net (code "37") (name "Net-(F1-P0)") (class "Default")
      (node (ref "D0") (pin "A") (pinfunction "A_A") (pintype "passive"))
      (node (ref "F1") (pin "MX1") (pinfunction "P0_MX1") (pintype "bidirectional"))
    )
    (net (code "38") (name "Net-(F2-P0)") (class "Default")
      (node (ref "D1") (pin "A") (pinfunction "A_A") (pintype "passive"))
      (node (ref "F2") (pin "MX1") (pinfunction "P0_MX1") (pintype "bidirectional"))
    )
    (net (code "39") (name "Net-(F3-P0)") (class "Default")
      (node (ref "D2") (pin "A") (pinfunction "A_A") (pintype "passive"))
      (node (ref "F3") (pin "MX1") (pinfunction "P0_MX1") (pintype "bidirectional"))
    )
    (net (code "40") (name "Net-(F4-P0)") (class "Default")
      (node (ref "D3") (pin "A") (pinfunction "A_A") (pintype "passive"))
      (node (ref "F4") (pin "MX1") (pinfunction "P0_MX1") (pintype "bidirectional"))
    )
    (net (code "41") (name "Net-(F5-P0)") (class "Default")
      (node (ref "D4") (pin "A") (pinfunction "A_A") (pintype "passive"))
      (node (ref "F5") (pin "MX1") (pinfunction "P0_MX1") (pintype "bidirectional"))
    )
    (net (code "42") (name "Net-(F6-P0)") (class "Default")
      (node (ref "D5") (pin "A") (pinfunction "A_A") (pintype "passive"))
      (node (ref "F6") (pin "MX1") (pinfunction "P0_MX1") (pintype "bidirectional"))
    )
    (net (code "43") (name "Net-(F7-P0)") (class "Default")
      (node (ref "D6") (pin "A") (pinfunction "A_A") (pintype "passive"))
      (node (ref "F7") (pin "MX1") (pinfunction "P0_MX1") (pintype "bidirectional"))
    )
    (net (code "44") (name "Net-(F8-P0)") (class "Default")
      (node (ref "D7") (pin "A") (pinfunction "A_A") (pintype "passive"))
      (node (ref "F8") (pin "MX1") (pinfunction "P0_MX1") (pintype "bidirectional"))
    )
    (net (code "45") (name "Net-(F9-P0)") (class "Default")
      (node (ref "D8") (pin "A") (pinfunction "A_A") (pintype "passive"))
      (node (ref "F9") (pin "MX1") (pinfunction "P0_MX1") (pintype "bidirectional"))
    )
    (net (code "46") (name "Net-(F10-P0)") (class "Default")
      (node (ref "D9") (pin "A") (pinfunction "A_A") (pintype "passive"))
      (node (ref "F10") (pin "MX1") (pinfunction "P0_MX1") (pintype "bidirectional"))
    )
    (net (code "47") (name "Net-(F11-P0)") (class "Default")
      (node (ref "D10") (pin "A") (pinfunction "A_A") (pintype "passive"))
      (node (ref "F11") (pin "MX1") (pinfunction "P0_MX1") (pintype "bidirectional"))
    )
    (net (code "48") (name "Net-(F12-P0)") (class "Default")
      (node (ref "D11") (pin "A") (pinfunction "A_A") (pintype "passive"))
      (node (ref "F12") (pin "MX1") (pinfunction "P0_MX1") (pintype "bidirectional"))
    )
    (net (code "49") (name "Net-(F13-P0)") (class "Default")
      (node (ref "D12") (pin "A") (pinfunction "A_A") (pintype "passive"))
      (node (ref "F13") (pin "MX1") (pinfunction "P0_MX1") (pintype "bidirectional"))
    )
    (net (code "50") (name "Net-(F14-P0)") (class "Default")
      (node (ref "D13") (pin "A") (pinfunction "A_A") (pintype "passive"))
      (node (ref "F14") (pin "MX1") (pinfunction "P0_MX1") (pintype "bidirectional"))
    )
    (net (code "51") (name "Net-(F15-P0)") (class "Default")
      (node (ref "D14") (pin "A") (pinfunction "A_A") (pintype "passive"))
      (node (ref "F15") (pin "MX1") (pinfunction "P0_MX1") (pintype "bidirectional"))
    )
    (net (code "52") (name "Net-(F16-P0)") (class "Default")
      (node (ref "D15") (pin "A") (pinfunction "A_A") (pintype "passive"))
      (node (ref "F16") (pin "MX1") (pinfunction "P0_MX1") (pintype "bidirectional"))
    )
    (net (code "53") (name "Net-(FERRITE_VCC-Pad1)") (class "Default")
      (node (ref "FERRITE_VCC") (pin "1") (pinfunction "1_1") (pintype "passive"))
      (node (ref "FUSE") (pin "1") (pinfunction "1_1") (pintype "passive"))
    )
    (net (code "54") (name "Net-(MCU-D+)") (class "Default")
      (node (ref "D+") (pin "2") (pinfunction "2_2") (pintype "passive"))
      (node (ref "MCU") (pin "4") (pinfunction "D+_4") (pintype "bidirectional"))
    )
    (net (code "55") (name "Net-(MCU-D-)") (class "Default")
      (node (ref "D-") (pin "2") (pinfunction "2_2") (pintype "passive"))
      (node (ref "MCU") (pin "3") (pinfunction "D-_3") (pintype "bidirectional"))
    )
    (net (code "56") (name "Net-(MCU-PE2(~{HWB}))") (class "Default")
      (node (ref "MCU") (pin "33") (pinfunction "PE2(~{HWB})_33") (pintype "bidirectional"))
      (node (ref "R4") (pin "2") (pinfunction "2_2") (pintype "passive"))
    )
    (net (code "57") (name "Net-(MCU-UCAP)") (class "Default")
      (node (ref "C9") (pin "2") (pinfunction "2_2") (pintype "passive"))
      (node (ref "MCU") (pin "6") (pinfunction "UCAP_6") (pintype "bidirectional"))
    )
    (net (code "58") (name "Net-(MCU-XTAL1)") (class "Default")
      (node (ref "C1") (pin "2") (pinfunction "2_2") (pintype "passive"))
      (node (ref "MCU") (pin "17") (pinfunction "XTAL1_17") (pintype "bidirectional"))
      (node (ref "Q1") (pin "1") (pinfunction "1_1") (pintype "passive"))
    )
    (net (code "59") (name "Net-(MCU-XTAL2)") (class "Default")
      (node (ref "C2") (pin "2") (pinfunction "2_2") (pintype "passive"))
      (node (ref "MCU") (pin "16") (pinfunction "XTAL2_16") (pintype "bidirectional"))
      (node (ref "Q1") (pin "3") (pinfunction "2_3") (pintype "passive"))
    )
    (net (code "60") (name "Net-(MCU-~{RESET})") (class "Default")
      (node (ref "MCU") (pin "13") (pinfunction "~{RESET}_13") (pintype "bidirectional"))
      (node (ref "R3") (pin "2") (pinfunction "2_2") (pintype "passive"))
      (node (ref "S1") (pin "C") (pinfunction "NO_C") (pintype "passive"))
      (node (ref "S1") (pin "D") (pinfunction "NO_D") (pintype "passive"))
    )
    (net (code "61") (name "Net-(UGLOW1-DIN)") (class "Default")
      (node (ref "UGLOW1") (pin "P$4") (pinfunction "DIN_P$4") (pintype "power_in"))
      (node (ref "UGLOW2") (pin "P$2") (pinfunction "DOUT_P$2") (pintype "output"))
    )
    (net (code "62") (name "Net-(UGLOW2-DIN)") (class "Default")
      (node (ref "UGLOW2") (pin "P$4") (pinfunction "DIN_P$4") (pintype "power_in"))
      (node (ref "UGLOW3") (pin "P$2") (pinfunction "DOUT_P$2") (pintype "output"))
    )
    (net (code "63") (name "Net-(UGLOW3-DIN)") (class "Default")
      (node (ref "R12") (pin "1") (pinfunction "1_1") (pintype "passive"))
      (node (ref "UGLOW3") (pin "P$4") (pinfunction "DIN_P$4") (pintype "power_in"))
    )
    (net (code "64") (name "unconnected-(DRIVER-CS5-Pad21)") (class "Default")
      (node (ref "DRIVER") (pin "21") (pinfunction "CS5_21") (pintype "bidirectional"))
    )
    (net (code "65") (name "unconnected-(DRIVER-CS6-Pad22)") (class "Default")
      (node (ref "DRIVER") (pin "22") (pinfunction "CS6_22") (pintype "bidirectional"))
    )
    (net (code "66") (name "unconnected-(DRIVER-CS7-Pad23)") (class "Default")
      (node (ref "DRIVER") (pin "23") (pinfunction "CS7_23") (pintype "bidirectional"))
    )
    (net (code "67") (name "unconnected-(DRIVER-CS8-Pad24)") (class "Default")
      (node (ref "DRIVER") (pin "24") (pinfunction "CS8_24") (pintype "bidirectional"))
    )
    (net (code "68") (name "unconnected-(DRIVER-CS9-Pad25)") (class "Default")
      (node (ref "DRIVER") (pin "25") (pinfunction "CS9_25") (pintype "bidirectional"))
    )
    (net (code "69") (name "unconnected-(DRIVER-CS10-Pad26)") (class "Default")
      (node (ref "DRIVER") (pin "26") (pinfunction "CS10_26") (pintype "bidirectional"))
    )
    (net (code "70") (name "unconnected-(DRIVER-CS11-Pad27)") (class "Default")
      (node (ref "DRIVER") (pin "27") (pinfunction "CS11_27") (pintype "bidirectional"))
    )
    (net (code "71") (name "unconnected-(DRIVER-CS12-Pad28)") (class "Default")
      (node (ref "DRIVER") (pin "28") (pinfunction "CS12_28") (pintype "bidirectional"))
    )
    (net (code "72") (name "unconnected-(DRIVER-CS13-Pad30)") (class "Default")
      (node (ref "DRIVER") (pin "30") (pinfunction "CS13_30") (pintype "bidirectional"))
    )
    (net (code "73") (name "unconnected-(DRIVER-CS14-Pad31)") (class "Default")
      (node (ref "DRIVER") (pin "31") (pinfunction "CS14_31") (pintype "bidirectional"))
    )
    (net (code "74") (name "unconnected-(DRIVER-CS15-Pad32)") (class "Default")
      (node (ref "DRIVER") (pin "32") (pinfunction "CS15_32") (pintype "bidirectional"))
    )
    (net (code "75") (name "unconnected-(DRIVER-CS16-Pad33)") (class "Default")
      (node (ref "DRIVER") (pin "33") (pinfunction "CS16_33") (pintype "bidirectional"))
    )
    (net (code "76") (name "unconnected-(DRIVER-INTB-Pad45)") (class "Default")
      (node (ref "DRIVER") (pin "45") (pinfunction "INTB_45") (pintype "bidirectional"))
    )
    (net (code "77") (name "unconnected-(DRIVER-NC_1-Pad1)") (class "Default")
      (node (ref "DRIVER") (pin "1") (pinfunction "NC_1_1") (pintype "bidirectional"))
    )
    (net (code "78") (name "unconnected-(DRIVER-NC_2-Pad36)") (class "Default")
      (node (ref "DRIVER") (pin "36") (pinfunction "NC_2_36") (pintype "bidirectional"))
    )
    (net (code "79") (name "unconnected-(DRIVER-SYNC-Pad40)") (class "Default")
      (node (ref "DRIVER") (pin "40") (pinfunction "SYNC_40") (pintype "bidirectional"))
    )
    (net (code "80") (name "unconnected-(J1-SBU1-PadA8)") (class "Default")
      (node (ref "J1") (pin "A8") (pinfunction "SBU1_A8") (pintype "bidirectional"))
    )
    (net (code "81") (name "unconnected-(J1-SBU2-PadB8)") (class "Default")
      (node (ref "J1") (pin "B8") (pinfunction "SBU2_B8") (pintype "bidirectional"))
    )
    (net (code "82") (name "unconnected-(MCU-AREF-Pad42)") (class "Default")
      (node (ref "MCU") (pin "42") (pinfunction "AREF_42") (pintype "bidirectional"))
    )
    (net (code "83") (name "unconnected-(MCU-PB0(SS{slash}PCINT0)-Pad8)") (class "Default")
      (node (ref "MCU") (pin "8") (pinfunction "PB0(SS/PCINT0)_8") (pintype "bidirectional"))
    )
    (net (code "84") (name "unconnected-(MCU-PB1(PCINT1{slash}SCLK)-Pad9)") (class "Default")
      (node (ref "MCU") (pin "9") (pinfunction "PB1(PCINT1/SCLK)_9") (pintype "bidirectional"))
    )
    (net (code "85") (name "unconnected-(MCU-PB2(PDI{slash}PCINT2{slash}MOSI)-Pad10)") (class "Default")
      (node (ref "MCU") (pin "10") (pinfunction "PB2(PDI/PCINT2/MOSI)_10") (pintype "bidirectional"))
    )
    (net (code "86") (name "unconnected-(MCU-PB7(PCINT7{slash}OC0A{slash}OC1C{slash}~{RTS})-Pad12)") (class "Default")
      (node (ref "MCU") (pin "12") (pinfunction "PB7(PCINT7/OC0A/OC1C/~{RTS})_12") (pintype "bidirectional"))
    )
    (net (code "87") (name "unconnected-(MCU-PD4(ICP1{slash}ADC8)-Pad25)") (class "Default")
      (node (ref "MCU") (pin "25") (pinfunction "PD4(ICP1/ADC8)_25") (pintype "bidirectional"))
    )
    (net (code "88") (name "unconnected-(MCU-PD5(XCLK1{slash}~{CTS})-Pad22)") (class "Default")
      (node (ref "MCU") (pin "22") (pinfunction "PD5(XCLK1/~{CTS})_22") (pintype "bidirectional"))
    )
    (net (code "89") (name "unconnected-(MCU-PE6(INT.6{slash}AIN0)-Pad1)") (class "Default")
      (node (ref "MCU") (pin "1") (pinfunction "PE6(INT.6/AIN0)_1") (pintype "bidirectional"))
    )
    (net (code "90") (name "unconnected-(MCU-PF0(ADC0)-Pad41)") (class "Default")
      (node (ref "MCU") (pin "41") (pinfunction "PF0(ADC0)_41") (pintype "bidirectional"))
    )
    (net (code "91") (name "unconnected-(MCU-PF1(ADC1)-Pad40)") (class "Default")
      (node (ref "MCU") (pin "40") (pinfunction "PF1(ADC1)_40") (pintype "bidirectional"))
    )
    (net (code "92") (name "unconnected-(MCU-PF4(ADC4{slash}TCK)-Pad39)") (class "Default")
      (node (ref "MCU") (pin "39") (pinfunction "PF4(ADC4/TCK)_39") (pintype "bidirectional"))
    )
    (net (code "93") (name "unconnected-(MCU-PF5(ADC5{slash}TMS)-Pad38)") (class "Default")
      (node (ref "MCU") (pin "38") (pinfunction "PF5(ADC5/TMS)_38") (pintype "bidirectional"))
    )
    (net (code "94") (name "unconnected-(MCU-PF6(ADC6{slash}TDO)-Pad37)") (class "Default")
      (node (ref "MCU") (pin "37") (pinfunction "PF6(ADC6/TDO)_37") (pintype "bidirectional"))
    )
    (net (code "95") (name "unconnected-(MCU-PF7(ADC7{slash}TDI)-Pad36)") (class "Default")
      (node (ref "MCU") (pin "36") (pinfunction "PF7(ADC7/TDI)_36") (pintype "bidirectional"))
    )
    (net (code "96") (name "unconnected-(UGLOW1-DOUT-PadP$2)") (class "Default")
      (node (ref "UGLOW1") (pin "P$2") (pinfunction "DOUT_P$2") (pintype "output"))
    )
  )
)
